# Teensyboard.net
KiCad netlist of a schematic drawn in EAGLE
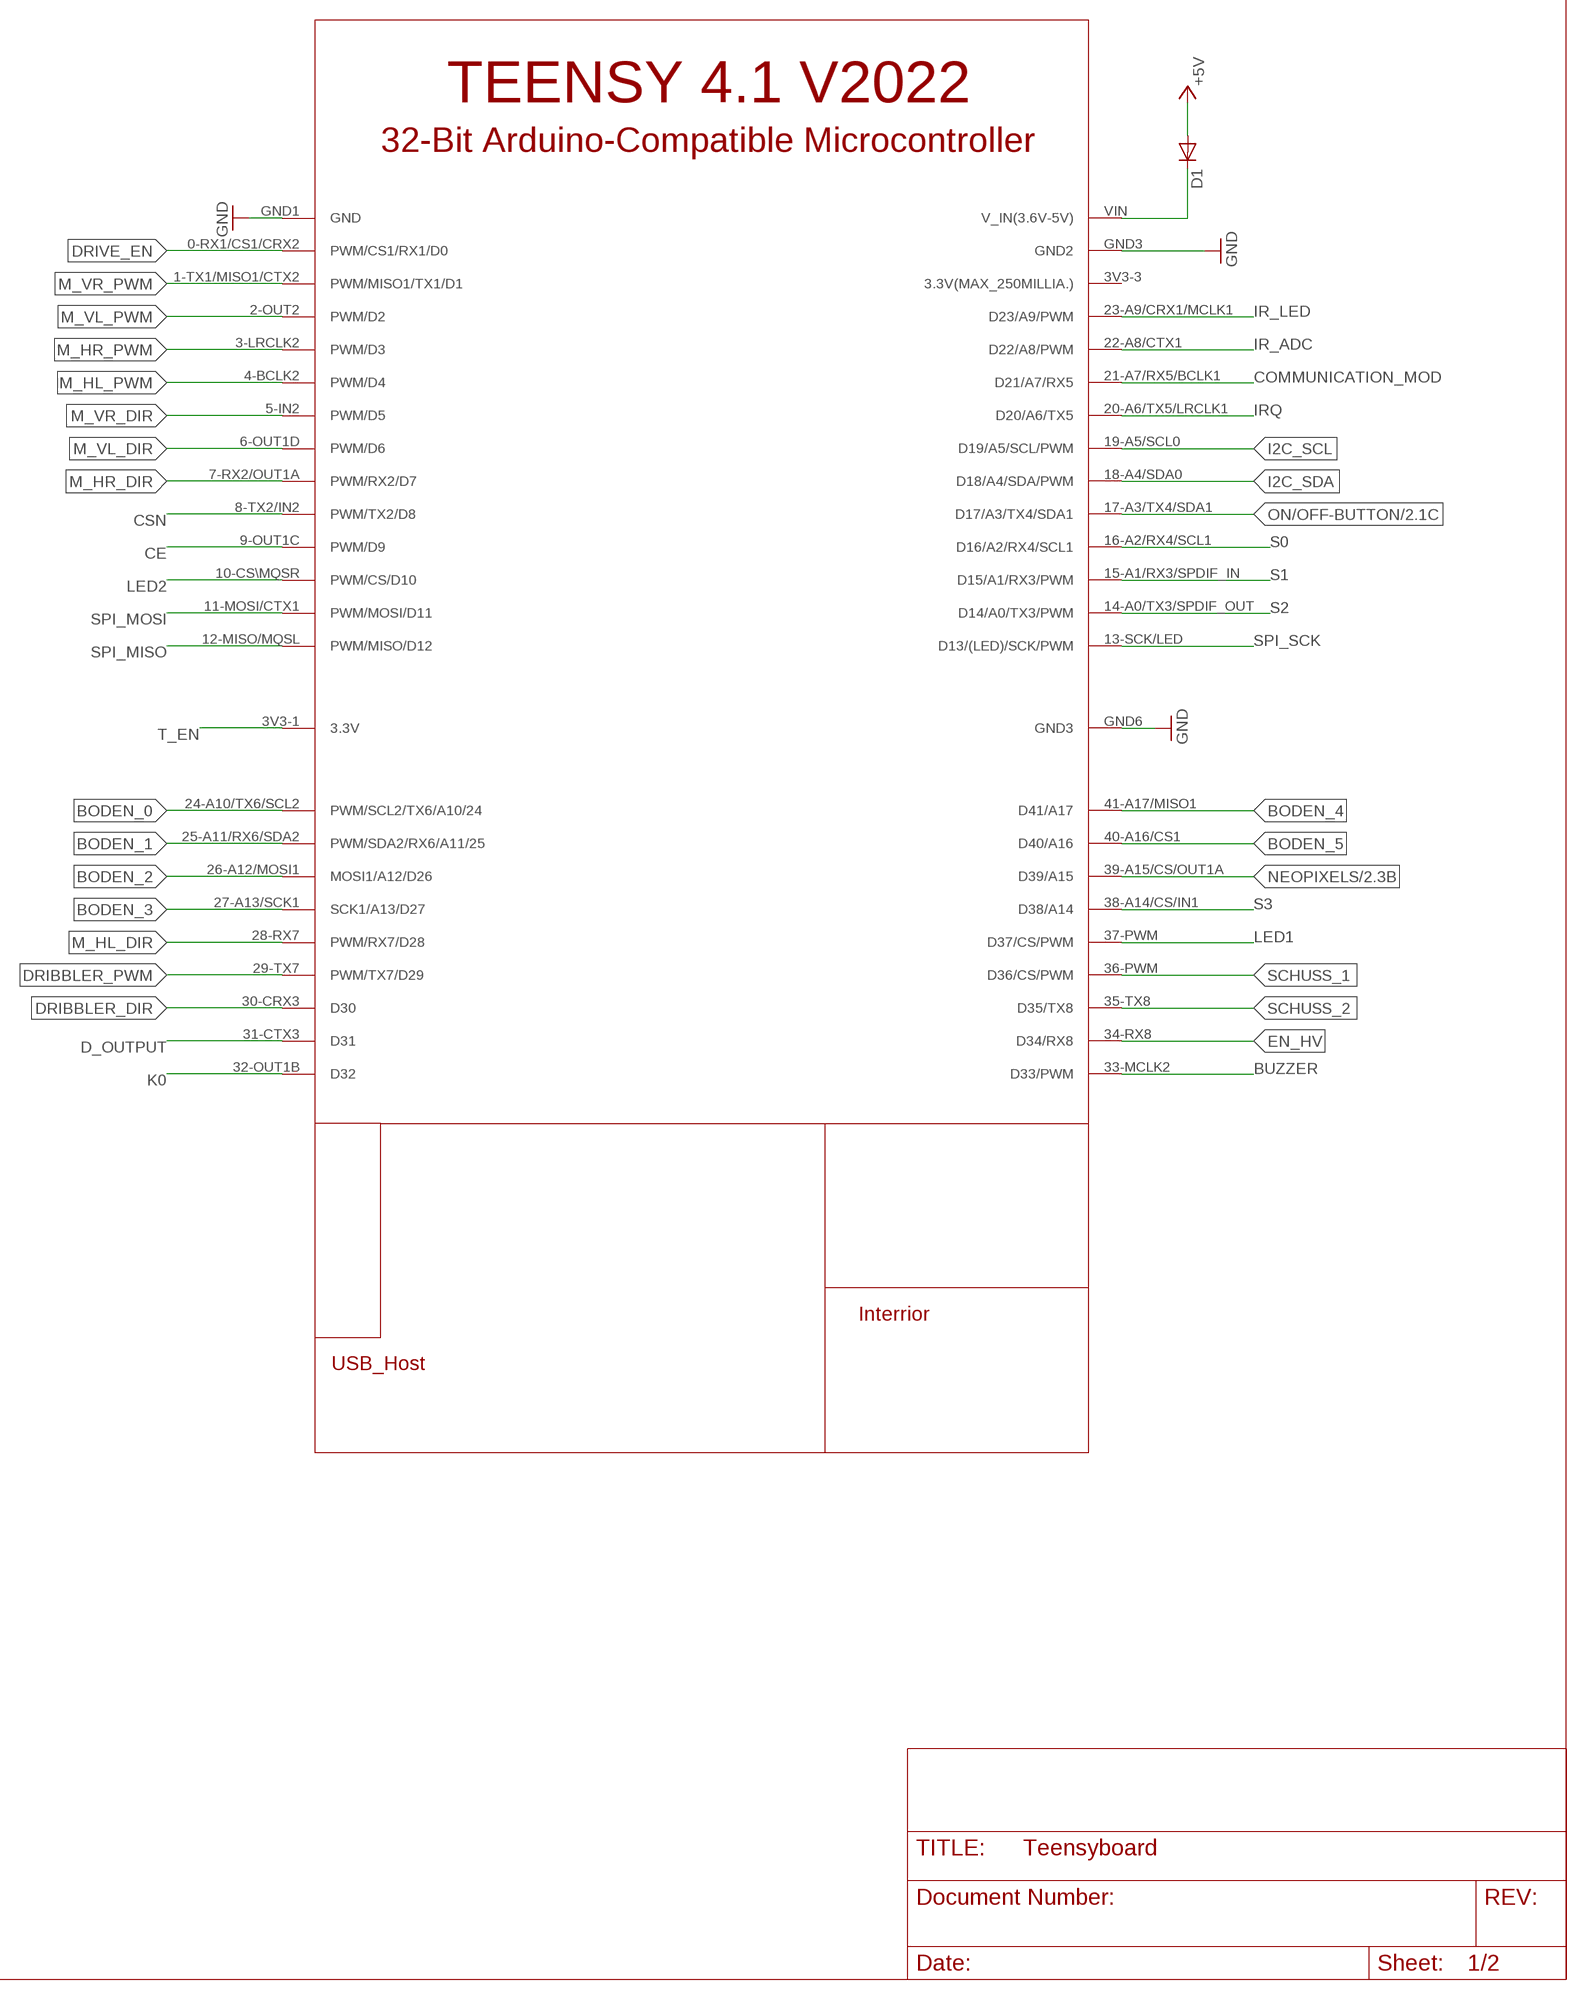
[diagram p0: schematic, sheet 1, part 1 of 2]
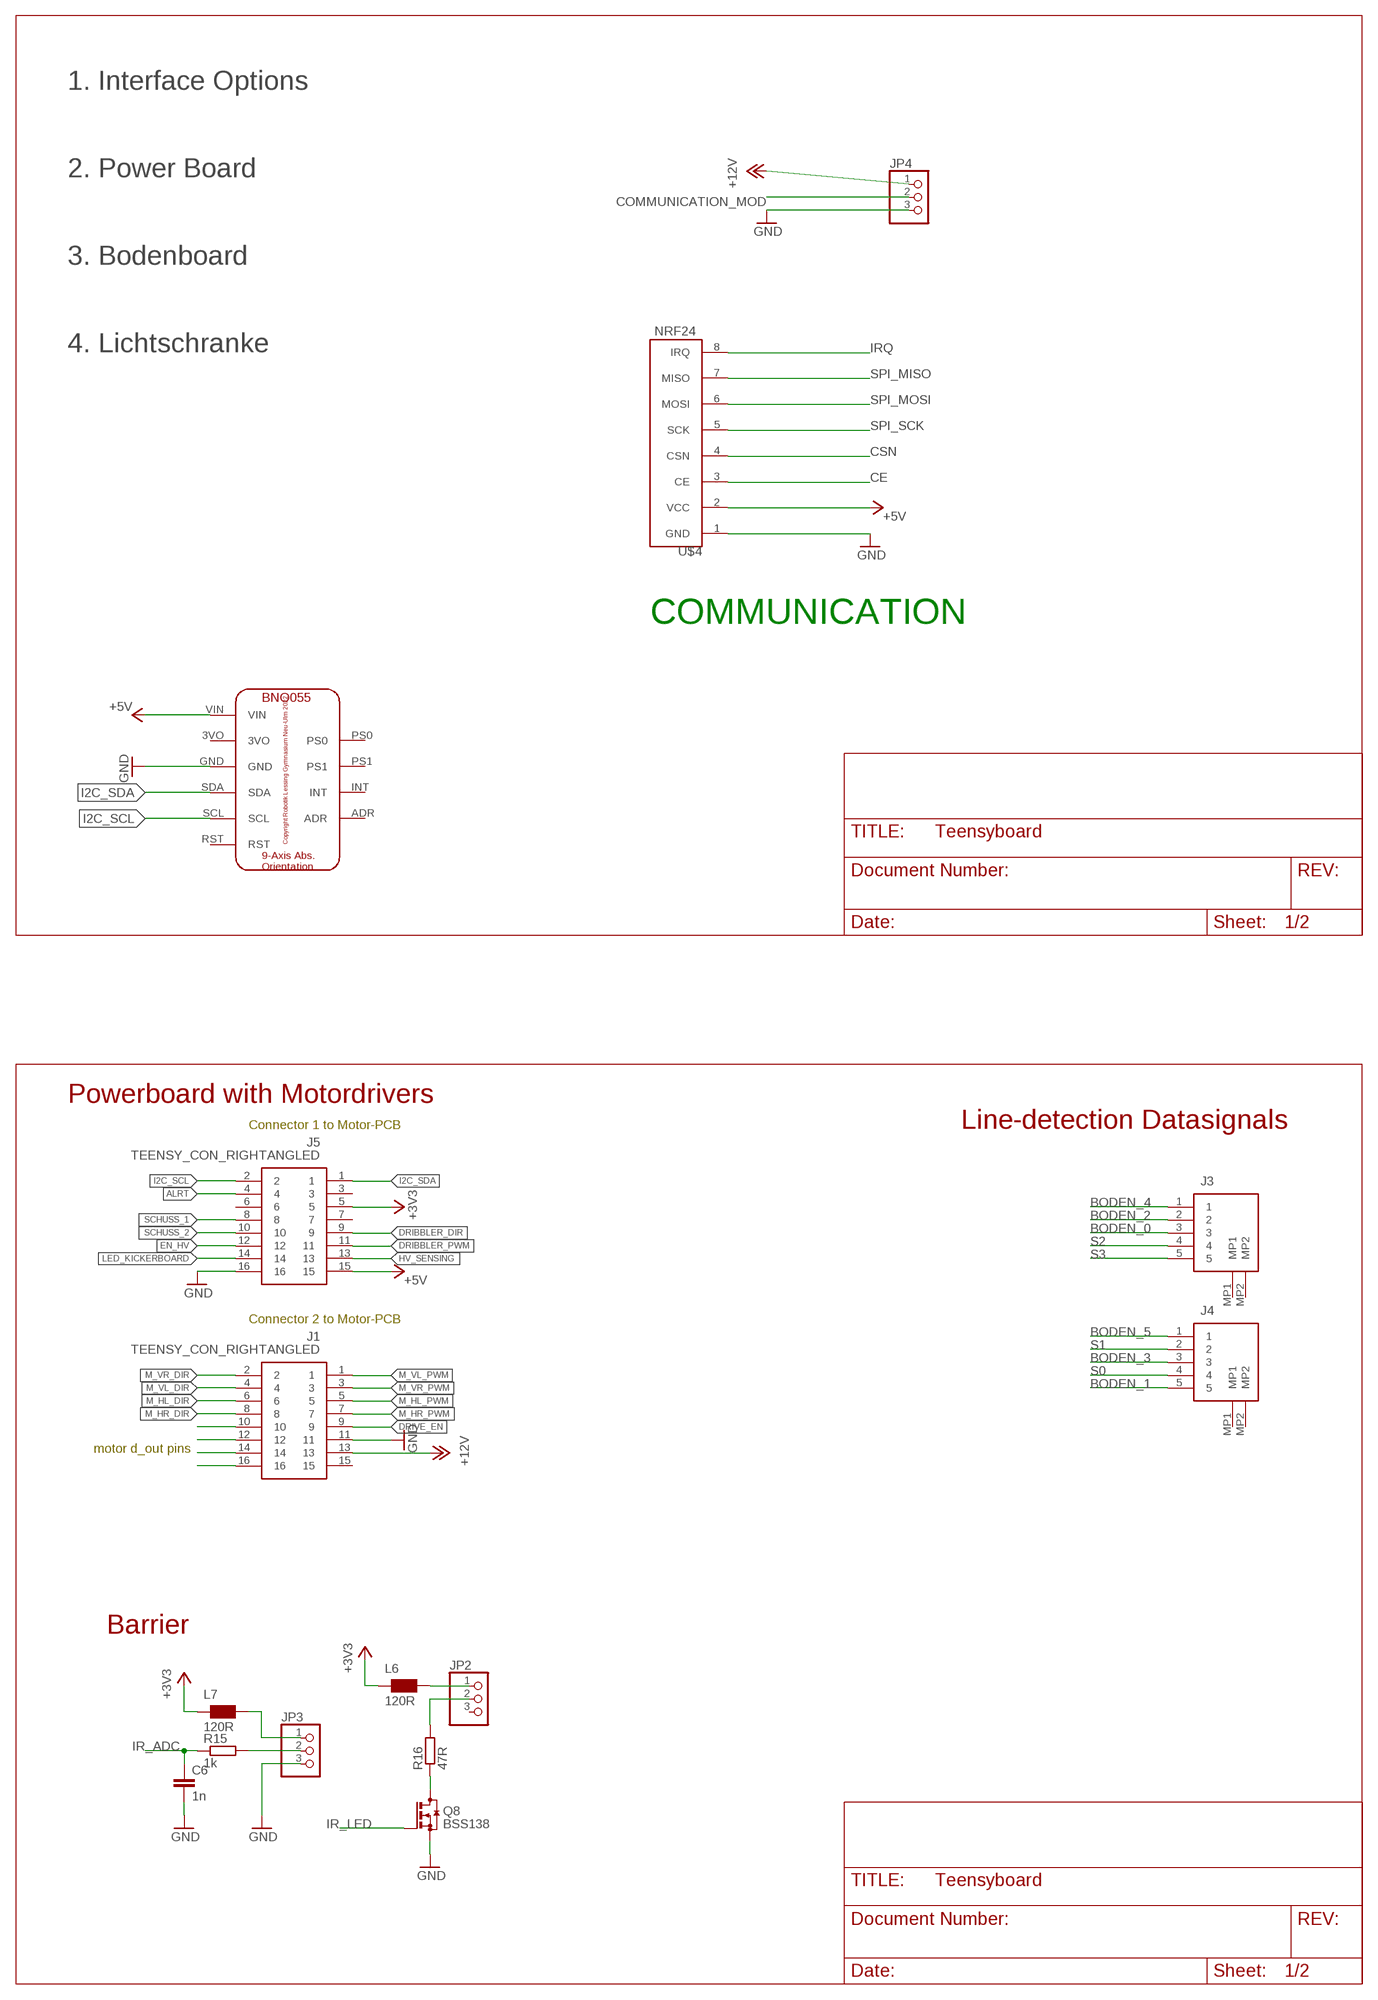
[diagram p1: schematic, sheet 1, part 2 of 2]
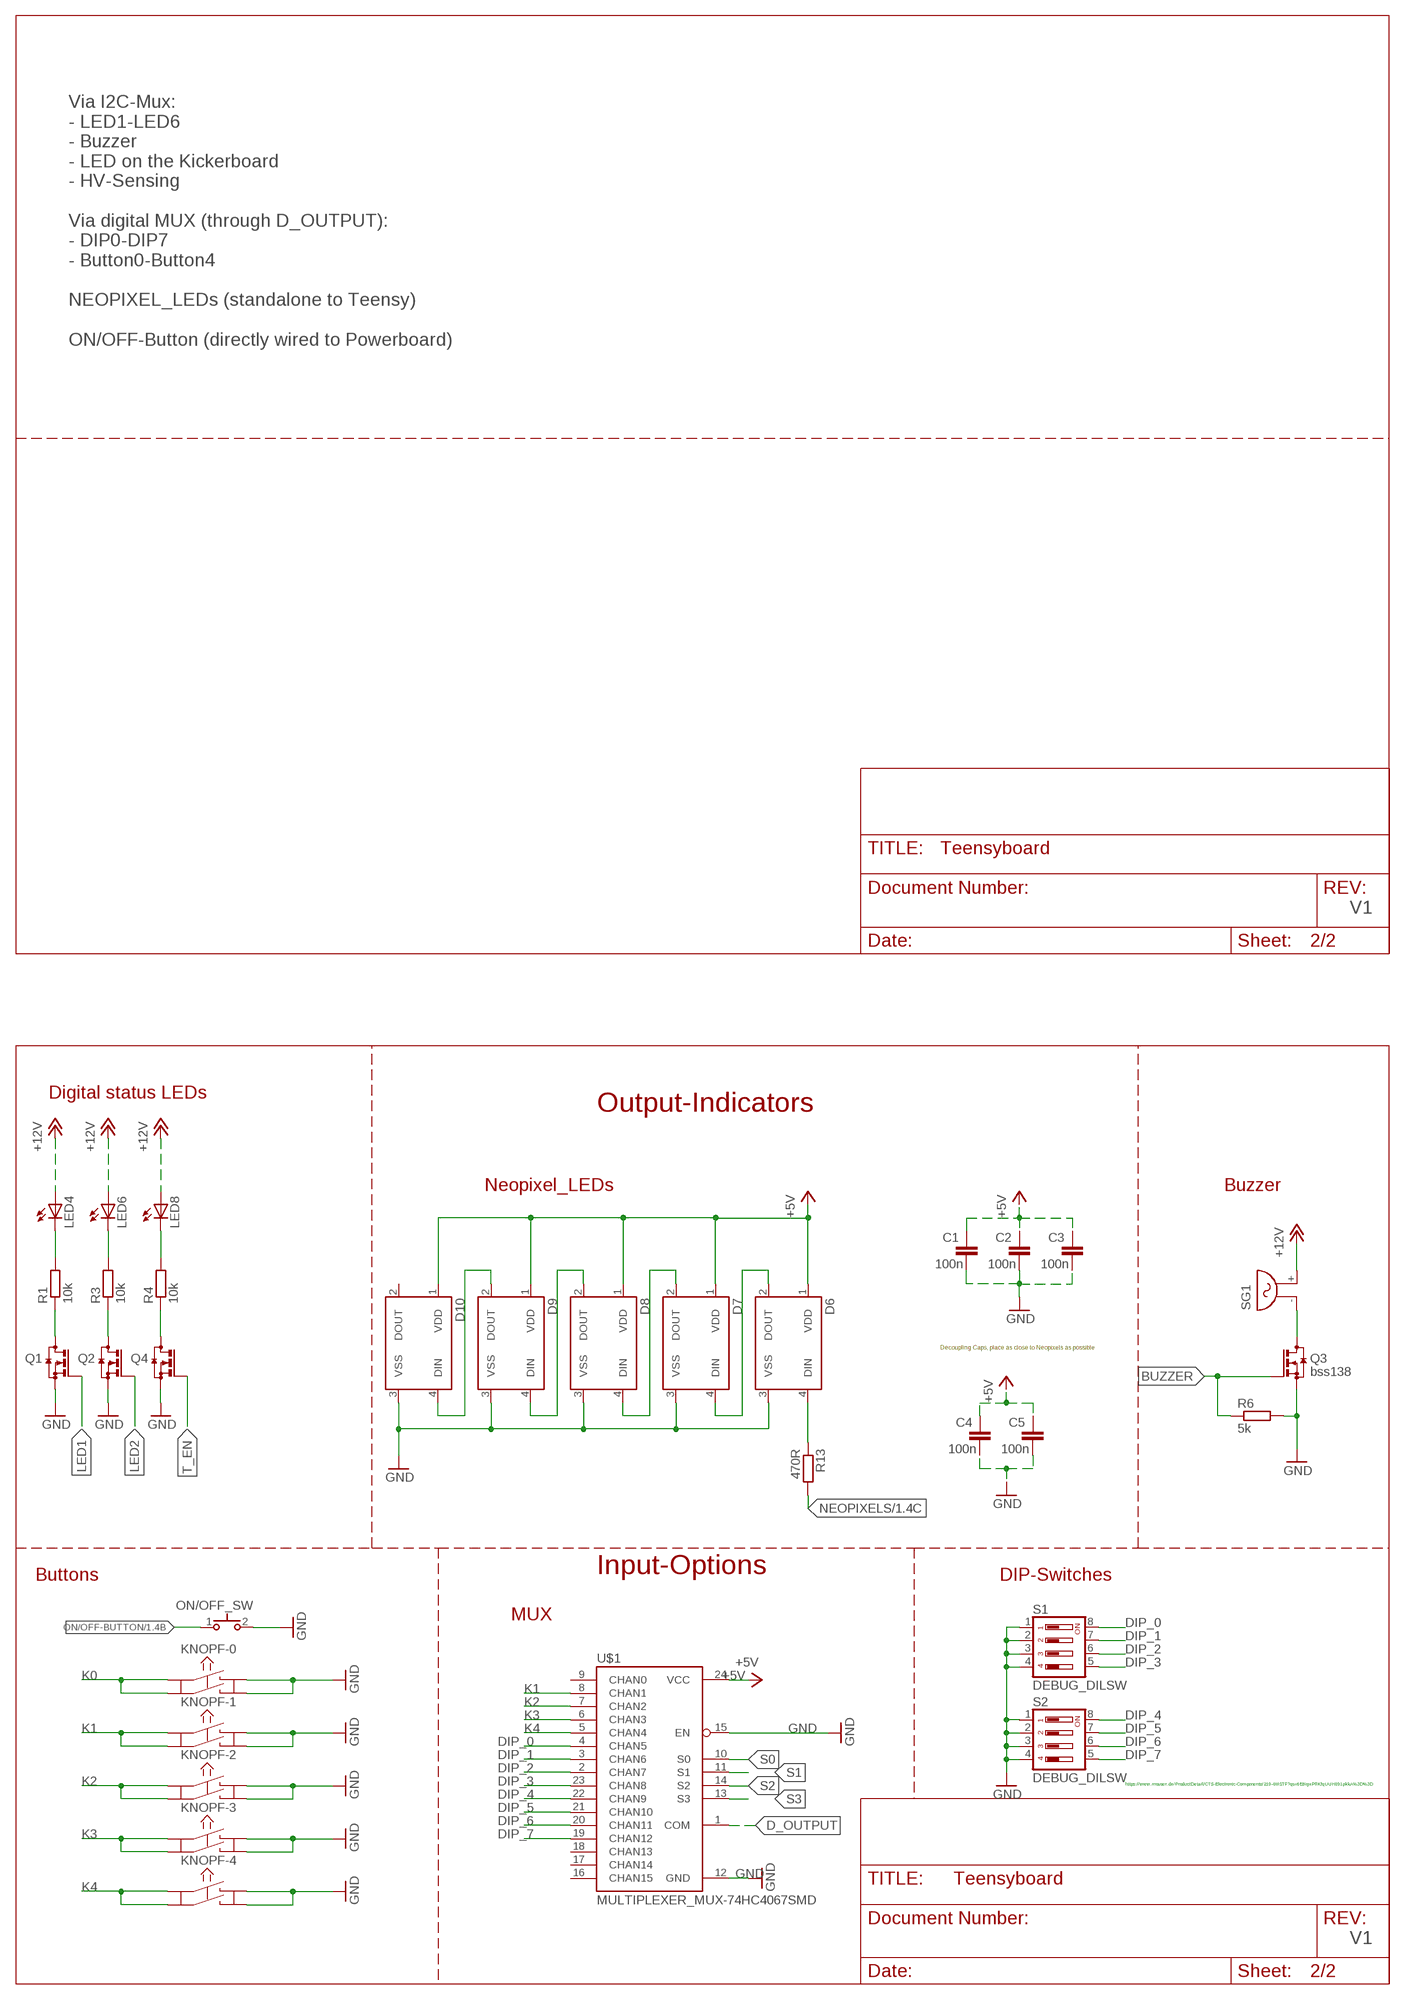
[diagram p2: schematic, sheet 2]

(export (version "E")
  (design (tool "Eeschema 10.0.6"))
  (components
    (comp (ref "C6")
      (value "1n")
      (footprint "eagle-import:C0603")
      (libsource (lib "eagle-import") (part "C-EUC0603"))
    )
    (comp (ref "D1")
      (value "DIODE-SMB")
      (footprint "eagle-import:SMB")
      (libsource (lib "eagle-import") (part "DIODE-SMB"))
    )
    (comp (ref "J1")
      (value "TEENSY_CON_RIGHTANGLED")
      (footprint "eagle-import:208659-1640_SHDRRA16W55P200_2X8_1800X1450X")
      (fields
        (field (name "MANUFACTURER_PART_NUMBER") "208659-1640")
        (field (name "MOUSER_PART_NUMBER") "538-208659-1640")
      )
      (libsource (lib "eagle-import") (part "TEENSY_CON_RIGHTANGLED"))
    )
    (comp (ref "J3")
      (value "5PIN_1MM_CON")
      (footprint "eagle-import:2035600503")
      (fields
        (field (name "MANUFACTURER_PART_NUMBER") "203560-0503")
        (field (name "MOUSER_PART_NUMBER") "538-203560-0503")
      )
      (libsource (lib "eagle-import") (part "5PIN_1MM_CON"))
    )
    (comp (ref "J4")
      (value "5PIN_1MM_CON")
      (footprint "eagle-import:2035600503")
      (fields
        (field (name "MANUFACTURER_PART_NUMBER") "203560-0503")
        (field (name "MOUSER_PART_NUMBER") "538-203560-0503")
      )
      (libsource (lib "eagle-import") (part "5PIN_1MM_CON"))
    )
    (comp (ref "J5")
      (value "TEENSY_CON_RIGHTANGLED")
      (footprint "eagle-import:208659-1640_SHDRRA16W55P200_2X8_1800X1450X")
      (fields
        (field (name "MANUFACTURER_PART_NUMBER") "208659-1640")
        (field (name "MOUSER_PART_NUMBER") "538-208659-1640")
      )
      (libsource (lib "eagle-import") (part "TEENSY_CON_RIGHTANGLED"))
    )
    (comp (ref "JP2")
      (value "PINHD-1X3")
      (footprint "eagle-import:1X03")
      (libsource (lib "eagle-import") (part "PINHD-1X3"))
    )
    (comp (ref "JP3")
      (value "PINHD-1X3")
      (footprint "eagle-import:1X03")
      (libsource (lib "eagle-import") (part "PINHD-1X3"))
    )
    (comp (ref "JP4")
      (value "PINHD-1X3")
      (footprint "eagle-import:1X03")
      (libsource (lib "eagle-import") (part "PINHD-1X3"))
    )
    (comp (ref "L6")
      (value "120R")
      (footprint "eagle-import:0603")
      (libsource (lib "eagle-import") (part "WE-CBF_0603"))
    )
    (comp (ref "L7")
      (value "120R")
      (footprint "eagle-import:0603")
      (libsource (lib "eagle-import") (part "WE-CBF_0603"))
    )
    (comp (ref "Q8")
      (value "BSS138")
      (footprint "eagle-import:SOT23")
      (libsource (lib "eagle-import") (part "BSS123"))
    )
    (comp (ref "R15")
      (value "1k")
      (footprint "eagle-import:R0603")
      (libsource (lib "eagle-import") (part "R-EU_R0603"))
    )
    (comp (ref "R16")
      (value "47R")
      (footprint "eagle-import:R0603")
      (libsource (lib "eagle-import") (part "R-EU_R0603"))
    )
    (comp (ref "U$2")
      (value "BNO055")
      (footprint "eagle-import:BNO055")
      (libsource (lib "eagle-import") (part "BNO055"))
    )
    (comp (ref "U$3")
      (value "TEENSY_4.1_WO_EXTRAPINS")
      (footprint "eagle-import:TEENSY_4.1_WO_EXTRAPINS")
      (libsource (lib "eagle-import") (part "TEENSY_4.1_WO_EXTRAPINS"))
    )
    (comp (ref "U$4")
      (value "NRF24")
      (footprint "eagle-import:NRF24")
      (libsource (lib "eagle-import") (part "NRF24"))
    )
    (comp (ref "C1")
      (value "100n")
      (footprint "eagle-import:C0805")
      (libsource (lib "eagle-import") (part "C-EUC0805"))
    )
    (comp (ref "C2")
      (value "100n")
      (footprint "eagle-import:C0805")
      (libsource (lib "eagle-import") (part "C-EUC0805"))
    )
    (comp (ref "C3")
      (value "100n")
      (footprint "eagle-import:C0805")
      (libsource (lib "eagle-import") (part "C-EUC0805"))
    )
    (comp (ref "C4")
      (value "100n")
      (footprint "eagle-import:C0805")
      (libsource (lib "eagle-import") (part "C-EUC0805"))
    )
    (comp (ref "C5")
      (value "100n")
      (footprint "eagle-import:C0805")
      (libsource (lib "eagle-import") (part "C-EUC0805"))
    )
    (comp (ref "D6")
      (value "DEBUG_WS2812B")
      (footprint "eagle-import:SPARKFUN-LED_WS2812B")
      (libsource (lib "eagle-import") (part "DEBUG_WS2812B"))
    )
    (comp (ref "D7")
      (value "DEBUG_WS2812B")
      (footprint "eagle-import:SPARKFUN-LED_WS2812B")
      (libsource (lib "eagle-import") (part "DEBUG_WS2812B"))
    )
    (comp (ref "D8")
      (value "DEBUG_WS2812B")
      (footprint "eagle-import:SPARKFUN-LED_WS2812B")
      (libsource (lib "eagle-import") (part "DEBUG_WS2812B"))
    )
    (comp (ref "D9")
      (value "DEBUG_WS2812B")
      (footprint "eagle-import:SPARKFUN-LED_WS2812B")
      (libsource (lib "eagle-import") (part "DEBUG_WS2812B"))
    )
    (comp (ref "D10")
      (value "DEBUG_WS2812B")
      (footprint "eagle-import:SPARKFUN-LED_WS2812B")
      (libsource (lib "eagle-import") (part "DEBUG_WS2812B"))
    )
    (comp (ref "KNOPF-0")
      (value "KSM611A")
      (footprint "eagle-import:KSM611A")
      (libsource (lib "eagle-import") (part "KSM611A"))
    )
    (comp (ref "KNOPF-1")
      (value "KSM611A")
      (footprint "eagle-import:KSM611A")
      (libsource (lib "eagle-import") (part "KSM611A"))
    )
    (comp (ref "KNOPF-2")
      (value "KSM611A")
      (footprint "eagle-import:KSM611A")
      (libsource (lib "eagle-import") (part "KSM611A"))
    )
    (comp (ref "KNOPF-3")
      (value "KSM611A")
      (footprint "eagle-import:KSM611A")
      (libsource (lib "eagle-import") (part "KSM611A"))
    )
    (comp (ref "KNOPF-4")
      (value "KSM611A")
      (footprint "eagle-import:KSM611A")
      (libsource (lib "eagle-import") (part "KSM611A"))
    )
    (comp (ref "LED4")
      (value "POWER_LED-GREEN-CHIPLED_0805")
      (footprint "eagle-import:POWER_DISTRIBUTION_CHIPLED_0805")
      (fields (field (name "MF") "Würth Elektronik") (field (name "MPN") "150080GS75000"))
      (libsource (lib "eagle-import") (part "POWER_LEDCHIPLED_0805-GREEN-"))
    )
    (comp (ref "LED6")
      (value "POWER_LED-GREEN-CHIPLED_0805")
      (footprint "eagle-import:POWER_DISTRIBUTION_CHIPLED_0805")
      (fields (field (name "MF") "Würth Elektronik") (field (name "MPN") "150080GS75000"))
      (libsource (lib "eagle-import") (part "POWER_LEDCHIPLED_0805-GREEN-"))
    )
    (comp (ref "LED8")
      (value "POWER_LED-GREEN-CHIPLED_0805")
      (footprint "eagle-import:POWER_DISTRIBUTION_CHIPLED_0805")
      (fields (field (name "MF") "Würth Elektronik") (field (name "MPN") "150080GS75000"))
      (libsource (lib "eagle-import") (part "POWER_LEDCHIPLED_0805-GREEN-"))
    )
    (comp (ref "ON/OFF_SW")
      (value "POWER_BUTTONS")
      (footprint "eagle-import:TIGERS_KT11")
      (libsource (lib "eagle-import") (part "POWER_BUTTONS"))
    )
    (comp (ref "Q1")
      (value "bss138")
      (footprint "eagle-import:TRANSISTOR-SMALL-SIGNAL_SOT23")
      (libsource (lib "eagle-import") (part "TRANSISTOR_BSS123"))
    )
    (comp (ref "Q2")
      (value "bss138")
      (footprint "eagle-import:TRANSISTOR-SMALL-SIGNAL_SOT23")
      (libsource (lib "eagle-import") (part "TRANSISTOR_BSS123"))
    )
    (comp (ref "Q3")
      (value "bss138")
      (footprint "eagle-import:TRANSISTOR-SMALL-SIGNAL_SOT23")
      (libsource (lib "eagle-import") (part "TRANSISTOR_BSS123"))
    )
    (comp (ref "Q4")
      (value "bss138")
      (footprint "eagle-import:TRANSISTOR-SMALL-SIGNAL_SOT23")
      (libsource (lib "eagle-import") (part "TRANSISTOR_BSS123"))
    )
    (comp (ref "R1")
      (value "10k")
      (footprint "eagle-import:R0603")
      (libsource (lib "eagle-import") (part "R-EU_R0603"))
    )
    (comp (ref "R3")
      (value "10k")
      (footprint "eagle-import:R0603")
      (libsource (lib "eagle-import") (part "R-EU_R0603"))
    )
    (comp (ref "R4")
      (value "10k")
      (footprint "eagle-import:R0603")
      (libsource (lib "eagle-import") (part "R-EU_R0603"))
    )
    (comp (ref "R6")
      (value "5k")
      (footprint "eagle-import:R0603")
      (libsource (lib "eagle-import") (part "R-EU_R0603"))
    )
    (comp (ref "R13")
      (value "470R")
      (footprint "eagle-import:R0603")
      (libsource (lib "eagle-import") (part "R-EU_R0603"))
    )
    (comp (ref "S1")
      (value "DEBUG_DILSW")
      (footprint "eagle-import:SWITCH-DIL_CTS-219-04")
      (libsource (lib "eagle-import") (part "DEBUG_DILSW"))
    )
    (comp (ref "S2")
      (value "DEBUG_DILSW")
      (footprint "eagle-import:SWITCH-DIL_CTS-219-04")
      (libsource (lib "eagle-import") (part "DEBUG_DILSW"))
    )
    (comp (ref "SG1")
      (value "DEBUG_BUZZER")
      (footprint "eagle-import:BUZZER_F_QMX")
      (libsource (lib "eagle-import") (part "DEBUG_BUZZER"))
    )
    (comp (ref "U$1")
      (value "MULTIPLEXER_MUX-74HC4067SMD")
      (footprint "eagle-import:SPARKFUN_SSOP24")
      (libsource (lib "eagle-import") (part "MULTIPLEXER_MUX-74HC4067SMD"))
    )
  )
  (nets
    (net (code "1") (name "+3V3") (class "Default")
      (node (ref "J5") (pin "5") (pinfunction "5_5") (pintype "bidirectional"))
      (node (ref "L6") (pin "1") (pinfunction "1_1") (pintype "passive"))
      (node (ref "L7") (pin "1") (pinfunction "1_1") (pintype "passive"))
    )
    (net (code "2") (name "+5V") (class "Default")
      (node (ref "C1") (pin "2") (pinfunction "2_2") (pintype "passive"))
      (node (ref "C2") (pin "2") (pinfunction "2_2") (pintype "passive"))
      (node (ref "C3") (pin "2") (pinfunction "2_2") (pintype "passive"))
      (node (ref "C4") (pin "2") (pinfunction "2_2") (pintype "passive"))
      (node (ref "C5") (pin "2") (pinfunction "2_2") (pintype "passive"))
      (node (ref "D1") (pin "A") (pinfunction "A_A") (pintype "passive"))
      (node (ref "D10") (pin "1") (pinfunction "VDD_1") (pintype "power_in"))
      (node (ref "D6") (pin "1") (pinfunction "VDD_1") (pintype "power_in"))
      (node (ref "D7") (pin "1") (pinfunction "VDD_1") (pintype "power_in"))
      (node (ref "D8") (pin "1") (pinfunction "VDD_1") (pintype "power_in"))
      (node (ref "D9") (pin "1") (pinfunction "VDD_1") (pintype "power_in"))
      (node (ref "J5") (pin "15") (pinfunction "15_15") (pintype "bidirectional"))
      (node (ref "U$1") (pin "24") (pinfunction "VCC_24") (pintype "bidirectional"))
      (node (ref "U$2") (pin "VIN") (pinfunction "VIN_VIN") (pintype "bidirectional"))
      (node (ref "U$4") (pin "2") (pinfunction "VCC_2") (pintype "bidirectional"))
    )
    (net (code "3") (name "+12V") (class "Default")
      (node (ref "J1") (pin "13") (pinfunction "13_13") (pintype "bidirectional"))
      (node (ref "JP4") (pin "1") (pinfunction "1_1") (pintype "passive"))
      (node (ref "LED4") (pin "A") (pinfunction "A_A") (pintype "passive"))
      (node (ref "LED6") (pin "A") (pinfunction "A_A") (pintype "passive"))
      (node (ref "LED8") (pin "A") (pinfunction "A_A") (pintype "passive"))
      (node (ref "SG1") (pin "+") (pinfunction "2_+") (pintype "passive"))
    )
    (net (code "4") (name "ALRT") (class "Default")
      (node (ref "J5") (pin "4") (pinfunction "4_4") (pintype "bidirectional"))
    )
    (net (code "5") (name "BODEN_0") (class "Default")
      (node (ref "J3") (pin "3") (pinfunction "3_3") (pintype "bidirectional"))
      (node (ref "U$3") (pin "24-A10/TX6/SCL2") (pinfunction "PWM/SCL2/TX6/A10/24_24-A10/TX6/SCL2") (pintype "bidirectional"))
    )
    (net (code "6") (name "BODEN_1") (class "Default")
      (node (ref "J4") (pin "5") (pinfunction "5_5") (pintype "bidirectional"))
      (node (ref "U$3") (pin "25-A11/RX6/SDA2") (pinfunction "PWM/SDA2/RX6/A11/25_25-A11/RX6/SDA2") (pintype "bidirectional"))
    )
    (net (code "7") (name "BODEN_2") (class "Default")
      (node (ref "J3") (pin "2") (pinfunction "2_2") (pintype "bidirectional"))
      (node (ref "U$3") (pin "26-A12/MOSI1") (pinfunction "MOSI1/A12/D26_26-A12/MOSI1") (pintype "bidirectional"))
    )
    (net (code "8") (name "BODEN_3") (class "Default")
      (node (ref "J4") (pin "3") (pinfunction "3_3") (pintype "bidirectional"))
      (node (ref "U$3") (pin "27-A13/SCK1") (pinfunction "SCK1/A13/D27_27-A13/SCK1") (pintype "bidirectional"))
    )
    (net (code "9") (name "BODEN_4") (class "Default")
      (node (ref "J3") (pin "1") (pinfunction "1_1") (pintype "bidirectional"))
      (node (ref "U$3") (pin "41-A17/MISO1") (pinfunction "D41/A17_41-A17/MISO1") (pintype "bidirectional"))
    )
    (net (code "10") (name "BODEN_5") (class "Default")
      (node (ref "J4") (pin "1") (pinfunction "1_1") (pintype "bidirectional"))
      (node (ref "U$3") (pin "40-A16/CS1") (pinfunction "D40/A16_40-A16/CS1") (pintype "bidirectional"))
    )
    (net (code "11") (name "BUZZER") (class "Default")
      (node (ref "Q3") (pin "1") (pinfunction "G_1") (pintype "passive"))
      (node (ref "R6") (pin "1") (pinfunction "1_1") (pintype "passive"))
      (node (ref "U$3") (pin "33-MCLK2") (pinfunction "D33/PWM_33-MCLK2") (pintype "bidirectional"))
    )
    (net (code "12") (name "CE") (class "Default")
      (node (ref "U$3") (pin "9-OUT1C") (pinfunction "PWM/D9_9-OUT1C") (pintype "bidirectional"))
      (node (ref "U$4") (pin "3") (pinfunction "CE_3") (pintype "bidirectional"))
    )
    (net (code "13") (name "COMMUNICATION_MOD") (class "Default")
      (node (ref "JP4") (pin "2") (pinfunction "2_2") (pintype "passive"))
      (node (ref "U$3") (pin "21-A7/RX5/BCLK1") (pinfunction "D21/A7/RX5_21-A7/RX5/BCLK1") (pintype "bidirectional"))
    )
    (net (code "14") (name "CSN") (class "Default")
      (node (ref "U$3") (pin "8-TX2/IN2") (pinfunction "PWM/TX2/D8_8-TX2/IN2") (pintype "bidirectional"))
      (node (ref "U$4") (pin "4") (pinfunction "CSN_4") (pintype "bidirectional"))
    )
    (net (code "15") (name "DIP_0") (class "Default")
      (node (ref "S1") (pin "8") (pinfunction "8_8") (pintype "passive"))
      (node (ref "U$1") (pin "4") (pinfunction "CHAN5_4") (pintype "bidirectional"))
    )
    (net (code "16") (name "DIP_1") (class "Default")
      (node (ref "S1") (pin "7") (pinfunction "7_7") (pintype "passive"))
      (node (ref "U$1") (pin "3") (pinfunction "CHAN6_3") (pintype "bidirectional"))
    )
    (net (code "17") (name "DIP_2") (class "Default")
      (node (ref "S1") (pin "6") (pinfunction "6_6") (pintype "passive"))
      (node (ref "U$1") (pin "2") (pinfunction "CHAN7_2") (pintype "bidirectional"))
    )
    (net (code "18") (name "DIP_3") (class "Default")
      (node (ref "S1") (pin "5") (pinfunction "5_5") (pintype "passive"))
      (node (ref "U$1") (pin "23") (pinfunction "CHAN8_23") (pintype "bidirectional"))
    )
    (net (code "19") (name "DIP_4") (class "Default")
      (node (ref "S2") (pin "8") (pinfunction "8_8") (pintype "passive"))
      (node (ref "U$1") (pin "22") (pinfunction "CHAN9_22") (pintype "bidirectional"))
    )
    (net (code "20") (name "DIP_5") (class "Default")
      (node (ref "S2") (pin "7") (pinfunction "7_7") (pintype "passive"))
      (node (ref "U$1") (pin "21") (pinfunction "CHAN10_21") (pintype "bidirectional"))
    )
    (net (code "21") (name "DIP_6") (class "Default")
      (node (ref "S2") (pin "6") (pinfunction "6_6") (pintype "passive"))
      (node (ref "U$1") (pin "20") (pinfunction "CHAN11_20") (pintype "bidirectional"))
    )
    (net (code "22") (name "DIP_7") (class "Default")
      (node (ref "S2") (pin "5") (pinfunction "5_5") (pintype "passive"))
      (node (ref "U$1") (pin "19") (pinfunction "CHAN12_19") (pintype "bidirectional"))
    )
    (net (code "23") (name "DRIBBLER_DIR") (class "Default")
      (node (ref "J5") (pin "9") (pinfunction "9_9") (pintype "bidirectional"))
      (node (ref "U$3") (pin "30-CRX3") (pinfunction "D30_30-CRX3") (pintype "bidirectional"))
    )
    (net (code "24") (name "DRIBBLER_PWM") (class "Default")
      (node (ref "J5") (pin "11") (pinfunction "11_11") (pintype "bidirectional"))
      (node (ref "U$3") (pin "29-TX7") (pinfunction "PWM/TX7/D29_29-TX7") (pintype "bidirectional"))
    )
    (net (code "25") (name "DRIVE_EN") (class "Default")
      (node (ref "J1") (pin "9") (pinfunction "9_9") (pintype "bidirectional"))
      (node (ref "U$3") (pin "0-RX1/CS1/CRX2") (pinfunction "PWM/CS1/RX1/D0_0-RX1/CS1/CRX2") (pintype "bidirectional"))
    )
    (net (code "26") (name "D_OUTPUT") (class "Default")
      (node (ref "U$1") (pin "1") (pinfunction "COM_1") (pintype "bidirectional"))
      (node (ref "U$3") (pin "31-CTX3") (pinfunction "D31_31-CTX3") (pintype "bidirectional"))
    )
    (net (code "27") (name "EN_HV") (class "Default")
      (node (ref "J5") (pin "12") (pinfunction "12_12") (pintype "bidirectional"))
      (node (ref "U$3") (pin "34-RX8") (pinfunction "D34/RX8_34-RX8") (pintype "bidirectional"))
    )
    (net (code "28") (name "GND") (class "Default")
      (node (ref "C1") (pin "1") (pinfunction "1_1") (pintype "passive"))
      (node (ref "C2") (pin "1") (pinfunction "1_1") (pintype "passive"))
      (node (ref "C3") (pin "1") (pinfunction "1_1") (pintype "passive"))
      (node (ref "C4") (pin "1") (pinfunction "1_1") (pintype "passive"))
      (node (ref "C5") (pin "1") (pinfunction "1_1") (pintype "passive"))
      (node (ref "C6") (pin "2") (pinfunction "2_2") (pintype "passive"))
      (node (ref "D10") (pin "3") (pinfunction "VSS_3") (pintype "power_in"))
      (node (ref "D6") (pin "3") (pinfunction "VSS_3") (pintype "power_in"))
      (node (ref "D7") (pin "3") (pinfunction "VSS_3") (pintype "power_in"))
      (node (ref "D8") (pin "3") (pinfunction "VSS_3") (pintype "power_in"))
      (node (ref "D9") (pin "3") (pinfunction "VSS_3") (pintype "power_in"))
      (node (ref "J1") (pin "11") (pinfunction "11_11") (pintype "bidirectional"))
      (node (ref "J5") (pin "16") (pinfunction "16_16") (pintype "bidirectional"))
      (node (ref "JP3") (pin "3") (pinfunction "3_3") (pintype "passive"))
      (node (ref "JP4") (pin "3") (pinfunction "3_3") (pintype "passive"))
      (node (ref "KNOPF-0") (pin "B") (pinfunction "B_B") (pintype "passive"))
      (node (ref "KNOPF-0") (pin "D") (pinfunction "D_D") (pintype "passive"))
      (node (ref "KNOPF-1") (pin "B") (pinfunction "B_B") (pintype "passive"))
      (node (ref "KNOPF-1") (pin "D") (pinfunction "D_D") (pintype "passive"))
      (node (ref "KNOPF-2") (pin "B") (pinfunction "B_B") (pintype "passive"))
      (node (ref "KNOPF-2") (pin "D") (pinfunction "D_D") (pintype "passive"))
      (node (ref "KNOPF-3") (pin "B") (pinfunction "B_B") (pintype "passive"))
      (node (ref "KNOPF-3") (pin "D") (pinfunction "D_D") (pintype "passive"))
      (node (ref "KNOPF-4") (pin "B") (pinfunction "B_B") (pintype "passive"))
      (node (ref "KNOPF-4") (pin "D") (pinfunction "D_D") (pintype "passive"))
      (node (ref "ON/OFF_SW") (pin "2") (pinfunction "2_2") (pintype "bidirectional"))
      (node (ref "Q1") (pin "2") (pinfunction "S_2") (pintype "passive"))
      (node (ref "Q2") (pin "2") (pinfunction "S_2") (pintype "passive"))
      (node (ref "Q3") (pin "2") (pinfunction "S_2") (pintype "passive"))
      (node (ref "Q4") (pin "2") (pinfunction "S_2") (pintype "passive"))
      (node (ref "Q8") (pin "2") (pinfunction "S_2") (pintype "passive"))
      (node (ref "R6") (pin "2") (pinfunction "2_2") (pintype "passive"))
      (node (ref "S1") (pin "1") (pinfunction "1_1") (pintype "passive"))
      (node (ref "S1") (pin "2") (pinfunction "2_2") (pintype "passive"))
      (node (ref "S1") (pin "3") (pinfunction "3_3") (pintype "passive"))
      (node (ref "S1") (pin "4") (pinfunction "4_4") (pintype "passive"))
      (node (ref "S2") (pin "1") (pinfunction "1_1") (pintype "passive"))
      (node (ref "S2") (pin "2") (pinfunction "2_2") (pintype "passive"))
      (node (ref "S2") (pin "3") (pinfunction "3_3") (pintype "passive"))
      (node (ref "S2") (pin "4") (pinfunction "4_4") (pintype "passive"))
      (node (ref "U$1") (pin "12") (pinfunction "GND_12") (pintype "bidirectional"))
      (node (ref "U$1") (pin "15") (pinfunction "EN_15") (pintype "input"))
      (node (ref "U$2") (pin "GND") (pinfunction "GND_GND") (pintype "bidirectional"))
      (node (ref "U$3") (pin "GND1") (pinfunction "GND_GND1") (pintype "bidirectional"))
      (node (ref "U$3") (pin "GND3") (pinfunction "GND2_GND3") (pintype "bidirectional"))
      (node (ref "U$3") (pin "GND6") (pinfunction "GND3_GND6") (pintype "bidirectional"))
      (node (ref "U$4") (pin "1") (pinfunction "GND_1") (pintype "bidirectional"))
    )
    (net (code "29") (name "HV_SENSING") (class "Default")
      (node (ref "J5") (pin "13") (pinfunction "13_13") (pintype "bidirectional"))
    )
    (net (code "30") (name "I2C_SCL") (class "Default")
      (node (ref "J5") (pin "2") (pinfunction "2_2") (pintype "bidirectional"))
      (node (ref "U$2") (pin "SCL") (pinfunction "SCL_SCL") (pintype "bidirectional"))
      (node (ref "U$3") (pin "19-A5/SCL0") (pinfunction "D19/A5/SCL/PWM_19-A5/SCL0") (pintype "bidirectional"))
    )
    (net (code "31") (name "I2C_SDA") (class "Default")
      (node (ref "J5") (pin "1") (pinfunction "1_1") (pintype "bidirectional"))
      (node (ref "U$2") (pin "SDA") (pinfunction "SDA_SDA") (pintype "bidirectional"))
      (node (ref "U$3") (pin "18-A4/SDA0") (pinfunction "D18/A4/SDA/PWM_18-A4/SDA0") (pintype "bidirectional"))
    )
    (net (code "32") (name "IRQ") (class "Default")
      (node (ref "U$3") (pin "20-A6/TX5/LRCLK1") (pinfunction "D20/A6/TX5_20-A6/TX5/LRCLK1") (pintype "bidirectional"))
      (node (ref "U$4") (pin "8") (pinfunction "IRQ_8") (pintype "bidirectional"))
    )
    (net (code "33") (name "IR_ADC") (class "Default")
      (node (ref "C6") (pin "1") (pinfunction "1_1") (pintype "passive"))
      (node (ref "R15") (pin "1") (pinfunction "1_1") (pintype "passive"))
      (node (ref "U$3") (pin "22-A8/CTX1") (pinfunction "D22/A8/PWM_22-A8/CTX1") (pintype "bidirectional"))
    )
    (net (code "34") (name "IR_LED") (class "Default")
      (node (ref "Q8") (pin "1") (pinfunction "G_1") (pintype "passive"))
      (node (ref "U$3") (pin "23-A9/CRX1/MCLK1") (pinfunction "D23/A9/PWM_23-A9/CRX1/MCLK1") (pintype "bidirectional"))
    )
    (net (code "35") (name "K0") (class "Default")
      (node (ref "KNOPF-0") (pin "A") (pinfunction "A_A") (pintype "passive"))
      (node (ref "KNOPF-0") (pin "C") (pinfunction "C_C") (pintype "passive"))
      (node (ref "U$3") (pin "32-OUT1B") (pinfunction "D32_32-OUT1B") (pintype "bidirectional"))
    )
    (net (code "36") (name "K1") (class "Default")
      (node (ref "KNOPF-1") (pin "A") (pinfunction "A_A") (pintype "passive"))
      (node (ref "KNOPF-1") (pin "C") (pinfunction "C_C") (pintype "passive"))
      (node (ref "U$1") (pin "8") (pinfunction "CHAN1_8") (pintype "bidirectional"))
    )
    (net (code "37") (name "K2") (class "Default")
      (node (ref "KNOPF-2") (pin "A") (pinfunction "A_A") (pintype "passive"))
      (node (ref "KNOPF-2") (pin "C") (pinfunction "C_C") (pintype "passive"))
      (node (ref "U$1") (pin "7") (pinfunction "CHAN2_7") (pintype "bidirectional"))
    )
    (net (code "38") (name "K3") (class "Default")
      (node (ref "KNOPF-3") (pin "A") (pinfunction "A_A") (pintype "passive"))
      (node (ref "KNOPF-3") (pin "C") (pinfunction "C_C") (pintype "passive"))
      (node (ref "U$1") (pin "6") (pinfunction "CHAN3_6") (pintype "bidirectional"))
    )
    (net (code "39") (name "K4") (class "Default")
      (node (ref "KNOPF-4") (pin "A") (pinfunction "A_A") (pintype "passive"))
      (node (ref "KNOPF-4") (pin "C") (pinfunction "C_C") (pintype "passive"))
      (node (ref "U$1") (pin "5") (pinfunction "CHAN4_5") (pintype "bidirectional"))
    )
    (net (code "40") (name "LED1") (class "Default")
      (node (ref "Q1") (pin "1") (pinfunction "G_1") (pintype "passive"))
      (node (ref "U$3") (pin "37-PWM") (pinfunction "D37/CS/PWM_37-PWM") (pintype "bidirectional"))
    )
    (net (code "41") (name "LED2") (class "Default")
      (node (ref "Q2") (pin "1") (pinfunction "G_1") (pintype "passive"))
      (node (ref "U$3") (pin "10-CS\\MQSR") (pinfunction "PWM/CS/D10_10-CS\\MQSR") (pintype "bidirectional"))
    )
    (net (code "42") (name "LED_KICKERBOARD") (class "Default")
      (node (ref "J5") (pin "14") (pinfunction "14_14") (pintype "bidirectional"))
    )
    (net (code "43") (name "M_HL_DIR") (class "Default")
      (node (ref "J1") (pin "6") (pinfunction "6_6") (pintype "bidirectional"))
      (node (ref "U$3") (pin "28-RX7") (pinfunction "PWM/RX7/D28_28-RX7") (pintype "bidirectional"))
    )
    (net (code "44") (name "M_HL_PWM") (class "Default")
      (node (ref "J1") (pin "5") (pinfunction "5_5") (pintype "bidirectional"))
      (node (ref "U$3") (pin "4-BCLK2") (pinfunction "PWM/D4_4-BCLK2") (pintype "bidirectional"))
    )
    (net (code "45") (name "M_HR_DIR") (class "Default")
      (node (ref "J1") (pin "8") (pinfunction "8_8") (pintype "bidirectional"))
      (node (ref "U$3") (pin "7-RX2/OUT1A") (pinfunction "PWM/RX2/D7_7-RX2/OUT1A") (pintype "bidirectional"))
    )
    (net (code "46") (name "M_HR_PWM") (class "Default")
      (node (ref "J1") (pin "7") (pinfunction "7_7") (pintype "bidirectional"))
      (node (ref "U$3") (pin "3-LRCLK2") (pinfunction "PWM/D3_3-LRCLK2") (pintype "bidirectional"))
    )
    (net (code "47") (name "M_VL_DIR") (class "Default")
      (node (ref "J1") (pin "4") (pinfunction "4_4") (pintype "bidirectional"))
      (node (ref "U$3") (pin "6-OUT1D") (pinfunction "PWM/D6_6-OUT1D") (pintype "bidirectional"))
    )
    (net (code "48") (name "M_VL_PWM") (class "Default")
      (node (ref "J1") (pin "1") (pinfunction "1_1") (pintype "bidirectional"))
      (node (ref "U$3") (pin "2-OUT2") (pinfunction "PWM/D2_2-OUT2") (pintype "bidirectional"))
    )
    (net (code "49") (name "M_VR_DIR") (class "Default")
      (node (ref "J1") (pin "2") (pinfunction "2_2") (pintype "bidirectional"))
      (node (ref "U$3") (pin "5-IN2") (pinfunction "PWM/D5_5-IN2") (pintype "bidirectional"))
    )
    (net (code "50") (name "M_VR_PWM") (class "Default")
      (node (ref "J1") (pin "3") (pinfunction "3_3") (pintype "bidirectional"))
      (node (ref "U$3") (pin "1-TX1/MISO1/CTX2") (pinfunction "PWM/MISO1/TX1/D1_1-TX1/MISO1/CTX2") (pintype "bidirectional"))
    )
    (net (code "51") (name "NEOPIXELS") (class "Default")
      (node (ref "R13") (pin "2") (pinfunction "2_2") (pintype "passive"))
      (node (ref "U$3") (pin "39-A15/CS/OUT1A") (pinfunction "D39/A15_39-A15/CS/OUT1A") (pintype "bidirectional"))
    )
    (net (code "52") (name "Net-(D6-DIN)") (class "Default")
      (node (ref "D6") (pin "4") (pinfunction "DIN_4") (pintype "input"))
      (node (ref "R13") (pin "1") (pinfunction "1_1") (pintype "passive"))
    )
    (net (code "53") (name "Net-(D6-DOUT)") (class "Default")
      (node (ref "D6") (pin "2") (pinfunction "DOUT_2") (pintype "output"))
      (node (ref "D7") (pin "4") (pinfunction "DIN_4") (pintype "input"))
    )
    (net (code "54") (name "Net-(D7-DOUT)") (class "Default")
      (node (ref "D7") (pin "2") (pinfunction "DOUT_2") (pintype "output"))
      (node (ref "D8") (pin "4") (pinfunction "DIN_4") (pintype "input"))
    )
    (net (code "55") (name "Net-(D8-DOUT)") (class "Default")
      (node (ref "D8") (pin "2") (pinfunction "DOUT_2") (pintype "output"))
      (node (ref "D9") (pin "4") (pinfunction "DIN_4") (pintype "input"))
    )
    (net (code "56") (name "Net-(D10-DIN)") (class "Default")
      (node (ref "D10") (pin "4") (pinfunction "DIN_4") (pintype "input"))
      (node (ref "D9") (pin "2") (pinfunction "DOUT_2") (pintype "output"))
    )
    (net (code "57") (name "Net-(JP2-Pad1)") (class "Default")
      (node (ref "JP2") (pin "1") (pinfunction "1_1") (pintype "passive"))
      (node (ref "L6") (pin "2") (pinfunction "2_2") (pintype "passive"))
    )
    (net (code "58") (name "Net-(JP2-Pad2)") (class "Default")
      (node (ref "JP2") (pin "2") (pinfunction "2_2") (pintype "passive"))
      (node (ref "R16") (pin "2") (pinfunction "2_2") (pintype "passive"))
    )
    (net (code "59") (name "Net-(JP3-Pad1)") (class "Default")
      (node (ref "JP3") (pin "1") (pinfunction "1_1") (pintype "passive"))
      (node (ref "L7") (pin "2") (pinfunction "2_2") (pintype "passive"))
    )
    (net (code "60") (name "Net-(JP3-Pad2)") (class "Default")
      (node (ref "JP3") (pin "2") (pinfunction "2_2") (pintype "passive"))
      (node (ref "R15") (pin "2") (pinfunction "2_2") (pintype "passive"))
    )
    (net (code "61") (name "Net-(LED4-PadC)") (class "Default")
      (node (ref "LED4") (pin "C") (pinfunction "C_C") (pintype "passive"))
      (node (ref "R1") (pin "2") (pinfunction "2_2") (pintype "passive"))
    )
    (net (code "62") (name "Net-(LED6-PadC)") (class "Default")
      (node (ref "LED6") (pin "C") (pinfunction "C_C") (pintype "passive"))
      (node (ref "R3") (pin "2") (pinfunction "2_2") (pintype "passive"))
    )
    (net (code "63") (name "Net-(LED8-PadC)") (class "Default")
      (node (ref "LED8") (pin "C") (pinfunction "C_C") (pintype "passive"))
      (node (ref "R4") (pin "2") (pinfunction "2_2") (pintype "passive"))
    )
    (net (code "64") (name "Net-(Q1-D)") (class "Default")
      (node (ref "Q1") (pin "3") (pinfunction "D_3") (pintype "passive"))
      (node (ref "R1") (pin "1") (pinfunction "1_1") (pintype "passive"))
    )
    (net (code "65") (name "Net-(Q2-D)") (class "Default")
      (node (ref "Q2") (pin "3") (pinfunction "D_3") (pintype "passive"))
      (node (ref "R3") (pin "1") (pinfunction "1_1") (pintype "passive"))
    )
    (net (code "66") (name "Net-(Q3-D)") (class "Default")
      (node (ref "Q3") (pin "3") (pinfunction "D_3") (pintype "passive"))
      (node (ref "SG1") (pin "-") (pinfunction "1_-") (pintype "passive"))
    )
    (net (code "67") (name "Net-(Q4-D)") (class "Default")
      (node (ref "Q4") (pin "3") (pinfunction "D_3") (pintype "passive"))
      (node (ref "R4") (pin "1") (pinfunction "1_1") (pintype "passive"))
    )
    (net (code "68") (name "Net-(Q8-D)") (class "Default")
      (node (ref "Q8") (pin "3") (pinfunction "D_3") (pintype "passive"))
      (node (ref "R16") (pin "1") (pinfunction "1_1") (pintype "passive"))
    )
    (net (code "69") (name "Net-(U$3-V_IN(3.6V-5V))") (class "Default")
      (node (ref "D1") (pin "C") (pinfunction "C_C") (pintype "passive"))
      (node (ref "U$3") (pin "VIN") (pinfunction "V_IN(3.6V-5V)_VIN") (pintype "bidirectional"))
    )
    (net (code "70") (name "ON{slash}OFF-BUTTON") (class "Default")
      (node (ref "ON/OFF_SW") (pin "1") (pinfunction "1_1") (pintype "bidirectional"))
      (node (ref "U$3") (pin "17-A3/TX4/SDA1") (pinfunction "D17/A3/TX4/SDA1_17-A3/TX4/SDA1") (pintype "bidirectional"))
    )
    (net (code "71") (name "S0") (class "Default")
      (node (ref "J4") (pin "4") (pinfunction "4_4") (pintype "bidirectional"))
      (node (ref "U$1") (pin "10") (pinfunction "S0_10") (pintype "input"))
      (node (ref "U$3") (pin "16-A2/RX4/SCL1") (pinfunction "D16/A2/RX4/SCL1_16-A2/RX4/SCL1") (pintype "bidirectional"))
    )
    (net (code "72") (name "S1") (class "Default")
      (node (ref "J4") (pin "2") (pinfunction "2_2") (pintype "bidirectional"))
      (node (ref "U$1") (pin "11") (pinfunction "S1_11") (pintype "input"))
      (node (ref "U$3") (pin "15-A1/RX3/SPDIF_IN") (pinfunction "D15/A1/RX3/PWM_15-A1/RX3/SPDIF_IN") (pintype "bidirectional"))
    )
    (net (code "73") (name "S2") (class "Default")
      (node (ref "J3") (pin "4") (pinfunction "4_4") (pintype "bidirectional"))
      (node (ref "U$1") (pin "14") (pinfunction "S2_14") (pintype "input"))
      (node (ref "U$3") (pin "14-A0/TX3/SPDIF_OUT") (pinfunction "D14/A0/TX3/PWM_14-A0/TX3/SPDIF_OUT") (pintype "bidirectional"))
    )
    (net (code "74") (name "S3") (class "Default")
      (node (ref "J3") (pin "5") (pinfunction "5_5") (pintype "bidirectional"))
      (node (ref "U$1") (pin "13") (pinfunction "S3_13") (pintype "input"))
      (node (ref "U$3") (pin "38-A14/CS/IN1") (pinfunction "D38/A14_38-A14/CS/IN1") (pintype "bidirectional"))
    )
    (net (code "75") (name "SCHUSS_1") (class "Default")
      (node (ref "J5") (pin "8") (pinfunction "8_8") (pintype "bidirectional"))
      (node (ref "U$3") (pin "36-PWM") (pinfunction "D36/CS/PWM_36-PWM") (pintype "bidirectional"))
    )
    (net (code "76") (name "SCHUSS_2") (class "Default")
      (node (ref "J5") (pin "10") (pinfunction "10_10") (pintype "bidirectional"))
      (node (ref "U$3") (pin "35-TX8") (pinfunction "D35/TX8_35-TX8") (pintype "bidirectional"))
    )
    (net (code "77") (name "SPI_MISO") (class "Default")
      (node (ref "U$3") (pin "12-MISO/MQSL") (pinfunction "PWM/MISO/D12_12-MISO/MQSL") (pintype "bidirectional"))
      (node (ref "U$4") (pin "7") (pinfunction "MISO_7") (pintype "bidirectional"))
    )
    (net (code "78") (name "SPI_MOSI") (class "Default")
      (node (ref "U$3") (pin "11-MOSI/CTX1") (pinfunction "PWM/MOSI/D11_11-MOSI/CTX1") (pintype "bidirectional"))
      (node (ref "U$4") (pin "6") (pinfunction "MOSI_6") (pintype "bidirectional"))
    )
    (net (code "79") (name "SPI_SCK") (class "Default")
      (node (ref "U$3") (pin "13-SCK/LED") (pinfunction "D13/(LED)/SCK/PWM_13-SCK/LED") (pintype "bidirectional"))
      (node (ref "U$4") (pin "5") (pinfunction "SCK_5") (pintype "bidirectional"))
    )
    (net (code "80") (name "T_EN") (class "Default")
      (node (ref "Q4") (pin "1") (pinfunction "G_1") (pintype "passive"))
      (node (ref "U$3") (pin "3V3-1") (pinfunction "3.3V_3V3-1") (pintype "bidirectional"))
    )
    (net (code "81") (name "unconnected-(D10-DOUT-Pad2)") (class "Default")
      (node (ref "D10") (pin "2") (pinfunction "DOUT_2") (pintype "output"))
    )
    (net (code "82") (name "unconnected-(J1-Pad10)") (class "Default")
      (node (ref "J1") (pin "10") (pinfunction "10_10") (pintype "bidirectional"))
    )
    (net (code "83") (name "unconnected-(J1-Pad12)") (class "Default")
      (node (ref "J1") (pin "12") (pinfunction "12_12") (pintype "bidirectional"))
    )
    (net (code "84") (name "unconnected-(J1-Pad14)") (class "Default")
      (node (ref "J1") (pin "14") (pinfunction "14_14") (pintype "bidirectional"))
    )
    (net (code "85") (name "unconnected-(J1-Pad15)") (class "Default")
      (node (ref "J1") (pin "15") (pinfunction "15_15") (pintype "bidirectional"))
    )
    (net (code "86") (name "unconnected-(J1-Pad16)") (class "Default")
      (node (ref "J1") (pin "16") (pinfunction "16_16") (pintype "bidirectional"))
    )
    (net (code "87") (name "unconnected-(J3-PadMP1)") (class "Default")
      (node (ref "J3") (pin "MP1") (pinfunction "MP1_MP1") (pintype "no_connect"))
    )
    (net (code "88") (name "unconnected-(J3-PadMP2)") (class "Default")
      (node (ref "J3") (pin "MP2") (pinfunction "MP2_MP2") (pintype "no_connect"))
    )
    (net (code "89") (name "unconnected-(J4-PadMP1)") (class "Default")
      (node (ref "J4") (pin "MP1") (pinfunction "MP1_MP1") (pintype "no_connect"))
    )
    (net (code "90") (name "unconnected-(J4-PadMP2)") (class "Default")
      (node (ref "J4") (pin "MP2") (pinfunction "MP2_MP2") (pintype "no_connect"))
    )
    (net (code "91") (name "unconnected-(J5-Pad3)") (class "Default")
      (node (ref "J5") (pin "3") (pinfunction "3_3") (pintype "bidirectional"))
    )
    (net (code "92") (name "unconnected-(J5-Pad6)") (class "Default")
      (node (ref "J5") (pin "6") (pinfunction "6_6") (pintype "bidirectional"))
    )
    (net (code "93") (name "unconnected-(J5-Pad7)") (class "Default")
      (node (ref "J5") (pin "7") (pinfunction "7_7") (pintype "bidirectional"))
    )
    (net (code "94") (name "unconnected-(JP2-Pad3)") (class "Default")
      (node (ref "JP2") (pin "3") (pinfunction "3_3") (pintype "passive"))
    )
    (net (code "95") (name "unconnected-(U$1-CHAN0-Pad9)") (class "Default")
      (node (ref "U$1") (pin "9") (pinfunction "CHAN0_9") (pintype "bidirectional"))
    )
    (net (code "96") (name "unconnected-(U$1-CHAN13-Pad18)") (class "Default")
      (node (ref "U$1") (pin "18") (pinfunction "CHAN13_18") (pintype "bidirectional"))
    )
    (net (code "97") (name "unconnected-(U$1-CHAN14-Pad17)") (class "Default")
      (node (ref "U$1") (pin "17") (pinfunction "CHAN14_17") (pintype "bidirectional"))
    )
    (net (code "98") (name "unconnected-(U$1-CHAN15-Pad16)") (class "Default")
      (node (ref "U$1") (pin "16") (pinfunction "CHAN15_16") (pintype "bidirectional"))
    )
    (net (code "99") (name "unconnected-(U$2-Pad3VO)") (class "Default")
      (node (ref "U$2") (pin "3VO") (pinfunction "3VO_3VO") (pintype "bidirectional"))
    )
    (net (code "100") (name "unconnected-(U$2-PadADR)") (class "Default")
      (node (ref "U$2") (pin "ADR") (pinfunction "ADR_ADR") (pintype "bidirectional"))
    )
    (net (code "101") (name "unconnected-(U$2-PadINT)") (class "Default")
      (node (ref "U$2") (pin "INT") (pinfunction "INT_INT") (pintype "bidirectional"))
    )
    (net (code "102") (name "unconnected-(U$2-PadPS0)") (class "Default")
      (node (ref "U$2") (pin "PS0") (pinfunction "PS0_PS0") (pintype "bidirectional"))
    )
    (net (code "103") (name "unconnected-(U$2-PadPS1)") (class "Default")
      (node (ref "U$2") (pin "PS1") (pinfunction "PS1_PS1") (pintype "bidirectional"))
    )
    (net (code "104") (name "unconnected-(U$2-PadRST)") (class "Default")
      (node (ref "U$2") (pin "RST") (pinfunction "RST_RST") (pintype "bidirectional"))
    )
    (net (code "105") (name "unconnected-(U$3-3.3V(MAX_250MILLIA.)-Pad3V3-3)") (class "Default")
      (node (ref "U$3") (pin "3V3-3") (pinfunction "3.3V(MAX_250MILLIA.)_3V3-3") (pintype "bidirectional"))
    )
  )
)
